# POR_1_0.net
KiCad netlist of a schematic drawn in EAGLE
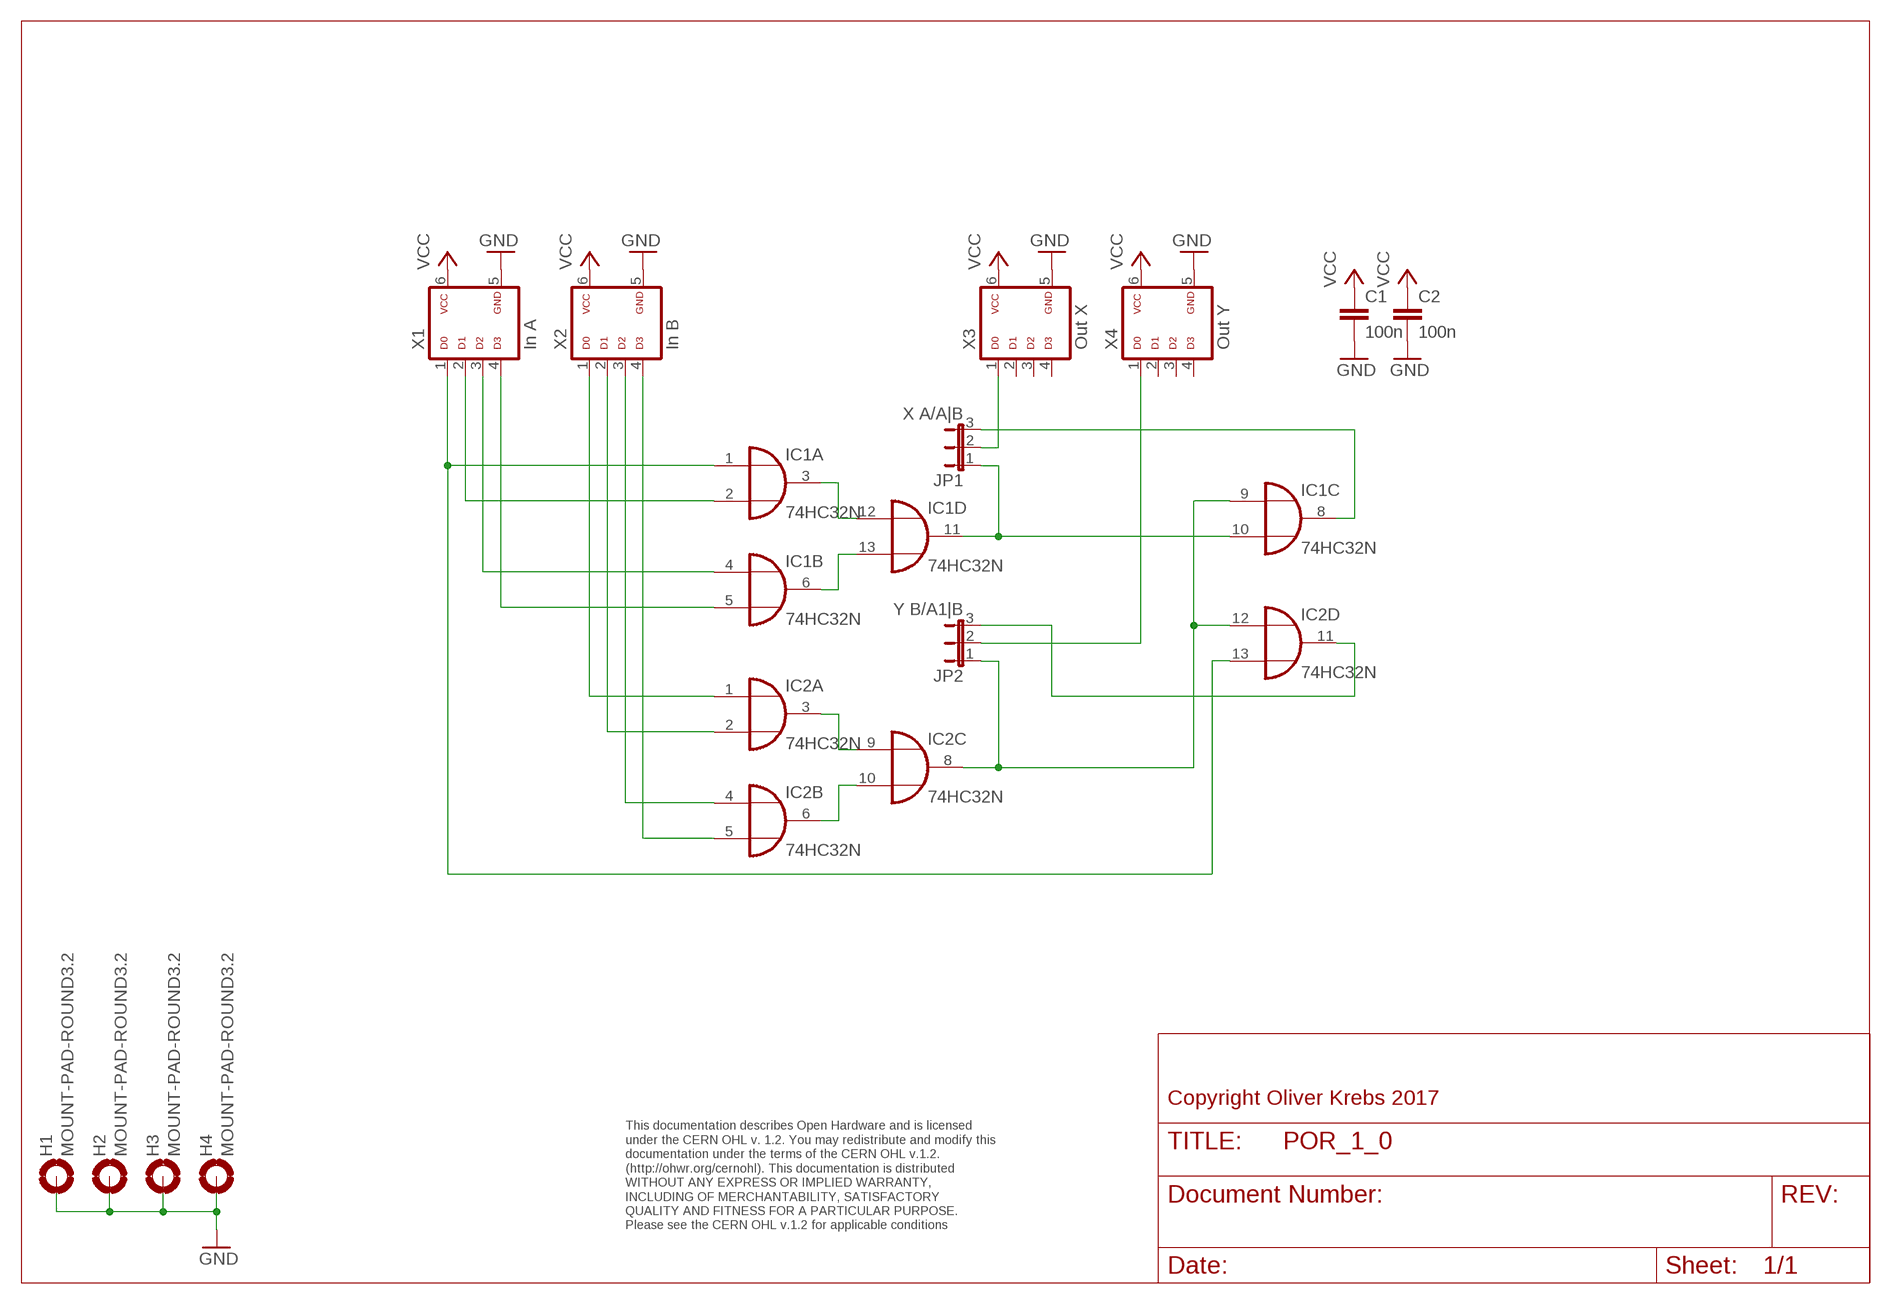
[diagram p0: schematic, sheet 1]

(export (version "E")
  (design (tool "Eeschema 10.0.6"))
  (components
    (comp (ref "C1")
      (value "100n")
      (footprint "eagle-import:C050-025X075")
      (libsource (lib "eagle-import") (part "C-EU050-025X075"))
    )
    (comp (ref "C2")
      (value "100n")
      (footprint "eagle-import:C050-025X075")
      (libsource (lib "eagle-import") (part "C-EU050-025X075"))
    )
    (comp (ref "H1")
      (value "MOUNT-PAD-ROUND3.2")
      (footprint "eagle-import:3,2-PAD")
      (libsource (lib "eagle-import") (part "MOUNT-PAD-ROUND3.2"))
    )
    (comp (ref "H2")
      (value "MOUNT-PAD-ROUND3.2")
      (footprint "eagle-import:3,2-PAD")
      (libsource (lib "eagle-import") (part "MOUNT-PAD-ROUND3.2"))
    )
    (comp (ref "H3")
      (value "MOUNT-PAD-ROUND3.2")
      (footprint "eagle-import:3,2-PAD")
      (libsource (lib "eagle-import") (part "MOUNT-PAD-ROUND3.2"))
    )
    (comp (ref "H4")
      (value "MOUNT-PAD-ROUND3.2")
      (footprint "eagle-import:3,2-PAD")
      (libsource (lib "eagle-import") (part "MOUNT-PAD-ROUND3.2"))
    )
    (comp (ref "IC1")
      (value "74HC32N")
      (footprint "eagle-import:DIL14")
      (libsource (lib "eagle-import") (part "7432NHC"))
    )
    (comp (ref "IC2")
      (value "74HC32N")
      (footprint "eagle-import:DIL14")
      (libsource (lib "eagle-import") (part "7432NHC"))
    )
    (comp (ref "JP1")
      (value "X A/A|B")
      (footprint "eagle-import:JP2-U")
      (libsource (lib "eagle-import") (part "JP2EJP2-U"))
    )
    (comp (ref "JP2")
      (value "Y B/A1|B")
      (footprint "eagle-import:JP2-U")
      (libsource (lib "eagle-import") (part "JP2EJP2-U"))
    )
    (comp (ref "X1")
      (value "In A")
      (footprint "eagle-import:ML-6")
      (libsource (lib "eagle-import") (part "ML6D"))
    )
    (comp (ref "X2")
      (value "In B")
      (footprint "eagle-import:ML-6")
      (libsource (lib "eagle-import") (part "ML6D"))
    )
    (comp (ref "X3")
      (value "Out X")
      (footprint "eagle-import:ML-6")
      (libsource (lib "eagle-import") (part "ML6D"))
    )
    (comp (ref "X4")
      (value "Out Y")
      (footprint "eagle-import:ML-6")
      (libsource (lib "eagle-import") (part "ML6D"))
    )
  )
  (nets
    (net (code "1") (name "GND") (class "Default")
      (node (ref "C1") (pin "2") (pinfunction "2_2") (pintype "passive"))
      (node (ref "C2") (pin "2") (pinfunction "2_2") (pintype "passive"))
      (node (ref "H1") (pin "B3,2") (pinfunction "MOUNT_B3,2") (pintype "passive"))
      (node (ref "H2") (pin "B3,2") (pinfunction "MOUNT_B3,2") (pintype "passive"))
      (node (ref "H3") (pin "B3,2") (pinfunction "MOUNT_B3,2") (pintype "passive"))
      (node (ref "H4") (pin "B3,2") (pinfunction "MOUNT_B3,2") (pintype "passive"))
      (node (ref "X1") (pin "5") (pinfunction "5_5") (pintype "passive"))
      (node (ref "X2") (pin "5") (pinfunction "5_5") (pintype "passive"))
      (node (ref "X3") (pin "5") (pinfunction "5_5") (pintype "passive"))
      (node (ref "X4") (pin "5") (pinfunction "5_5") (pintype "passive"))
    )
    (net (code "2") (name "Net-(IC1A-I0)") (class "Default")
      (node (ref "IC1") (pin "1") (pinfunction "I0_1") (pintype "input"))
      (node (ref "IC2") (pin "13") (pinfunction "I1_13") (pintype "input"))
      (node (ref "X1") (pin "1") (pinfunction "1_1") (pintype "passive"))
    )
    (net (code "3") (name "Net-(IC1A-I1)") (class "Default")
      (node (ref "IC1") (pin "2") (pinfunction "I1_2") (pintype "input"))
      (node (ref "X1") (pin "2") (pinfunction "2_2") (pintype "passive"))
    )
    (net (code "4") (name "Net-(IC1A-O)") (class "Default")
      (node (ref "IC1") (pin "12") (pinfunction "I0_12") (pintype "input"))
      (node (ref "IC1") (pin "3") (pinfunction "O_3") (pintype "output"))
    )
    (net (code "5") (name "Net-(IC1B-I0)") (class "Default")
      (node (ref "IC1") (pin "4") (pinfunction "I0_4") (pintype "input"))
      (node (ref "X1") (pin "3") (pinfunction "3_3") (pintype "passive"))
    )
    (net (code "6") (name "Net-(IC1B-I1)") (class "Default")
      (node (ref "IC1") (pin "5") (pinfunction "I1_5") (pintype "input"))
      (node (ref "X1") (pin "4") (pinfunction "4_4") (pintype "passive"))
    )
    (net (code "7") (name "Net-(IC1B-O)") (class "Default")
      (node (ref "IC1") (pin "13") (pinfunction "I1_13") (pintype "input"))
      (node (ref "IC1") (pin "6") (pinfunction "O_6") (pintype "output"))
    )
    (net (code "8") (name "Net-(IC1C-I0)") (class "Default")
      (node (ref "IC1") (pin "9") (pinfunction "I0_9") (pintype "input"))
      (node (ref "IC2") (pin "12") (pinfunction "I0_12") (pintype "input"))
      (node (ref "IC2") (pin "8") (pinfunction "O_8") (pintype "output"))
      (node (ref "JP2") (pin "1") (pinfunction "1_1") (pintype "passive"))
    )
    (net (code "9") (name "Net-(IC1C-I1)") (class "Default")
      (node (ref "IC1") (pin "10") (pinfunction "I1_10") (pintype "input"))
      (node (ref "IC1") (pin "11") (pinfunction "O_11") (pintype "output"))
      (node (ref "JP1") (pin "1") (pinfunction "1_1") (pintype "passive"))
    )
    (net (code "10") (name "Net-(IC1C-O)") (class "Default")
      (node (ref "IC1") (pin "8") (pinfunction "O_8") (pintype "output"))
      (node (ref "JP1") (pin "3") (pinfunction "3_3") (pintype "passive"))
    )
    (net (code "11") (name "Net-(IC2A-I0)") (class "Default")
      (node (ref "IC2") (pin "1") (pinfunction "I0_1") (pintype "input"))
      (node (ref "X2") (pin "1") (pinfunction "1_1") (pintype "passive"))
    )
    (net (code "12") (name "Net-(IC2A-I1)") (class "Default")
      (node (ref "IC2") (pin "2") (pinfunction "I1_2") (pintype "input"))
      (node (ref "X2") (pin "2") (pinfunction "2_2") (pintype "passive"))
    )
    (net (code "13") (name "Net-(IC2A-O)") (class "Default")
      (node (ref "IC2") (pin "3") (pinfunction "O_3") (pintype "output"))
      (node (ref "IC2") (pin "9") (pinfunction "I0_9") (pintype "input"))
    )
    (net (code "14") (name "Net-(IC2B-I0)") (class "Default")
      (node (ref "IC2") (pin "4") (pinfunction "I0_4") (pintype "input"))
      (node (ref "X2") (pin "3") (pinfunction "3_3") (pintype "passive"))
    )
    (net (code "15") (name "Net-(IC2B-I1)") (class "Default")
      (node (ref "IC2") (pin "5") (pinfunction "I1_5") (pintype "input"))
      (node (ref "X2") (pin "4") (pinfunction "4_4") (pintype "passive"))
    )
    (net (code "16") (name "Net-(IC2B-O)") (class "Default")
      (node (ref "IC2") (pin "10") (pinfunction "I1_10") (pintype "input"))
      (node (ref "IC2") (pin "6") (pinfunction "O_6") (pintype "output"))
    )
    (net (code "17") (name "Net-(IC2D-O)") (class "Default")
      (node (ref "IC2") (pin "11") (pinfunction "O_11") (pintype "output"))
      (node (ref "JP2") (pin "3") (pinfunction "3_3") (pintype "passive"))
    )
    (net (code "18") (name "Net-(JP1-Pad2)") (class "Default")
      (node (ref "JP1") (pin "2") (pinfunction "2_2") (pintype "passive"))
      (node (ref "X3") (pin "1") (pinfunction "1_1") (pintype "passive"))
    )
    (net (code "19") (name "Net-(JP2-Pad2)") (class "Default")
      (node (ref "JP2") (pin "2") (pinfunction "2_2") (pintype "passive"))
      (node (ref "X4") (pin "1") (pinfunction "1_1") (pintype "passive"))
    )
    (net (code "20") (name "VCC") (class "Default")
      (node (ref "C1") (pin "1") (pinfunction "1_1") (pintype "passive"))
      (node (ref "C2") (pin "1") (pinfunction "1_1") (pintype "passive"))
      (node (ref "X1") (pin "6") (pinfunction "6_6") (pintype "passive"))
      (node (ref "X2") (pin "6") (pinfunction "6_6") (pintype "passive"))
      (node (ref "X3") (pin "6") (pinfunction "6_6") (pintype "passive"))
      (node (ref "X4") (pin "6") (pinfunction "6_6") (pintype "passive"))
    )
    (net (code "21") (name "unconnected-(X3-Pad2)") (class "Default")
      (node (ref "X3") (pin "2") (pinfunction "2_2") (pintype "passive"))
    )
    (net (code "22") (name "unconnected-(X3-Pad3)") (class "Default")
      (node (ref "X3") (pin "3") (pinfunction "3_3") (pintype "passive"))
    )
    (net (code "23") (name "unconnected-(X3-Pad4)") (class "Default")
      (node (ref "X3") (pin "4") (pinfunction "4_4") (pintype "passive"))
    )
    (net (code "24") (name "unconnected-(X4-Pad2)") (class "Default")
      (node (ref "X4") (pin "2") (pinfunction "2_2") (pintype "passive"))
    )
    (net (code "25") (name "unconnected-(X4-Pad3)") (class "Default")
      (node (ref "X4") (pin "3") (pinfunction "3_3") (pintype "passive"))
    )
    (net (code "26") (name "unconnected-(X4-Pad4)") (class "Default")
      (node (ref "X4") (pin "4") (pinfunction "4_4") (pintype "passive"))
    )
  )
)
